# schematic.net
KiCad netlist of a schematic drawn in EAGLE
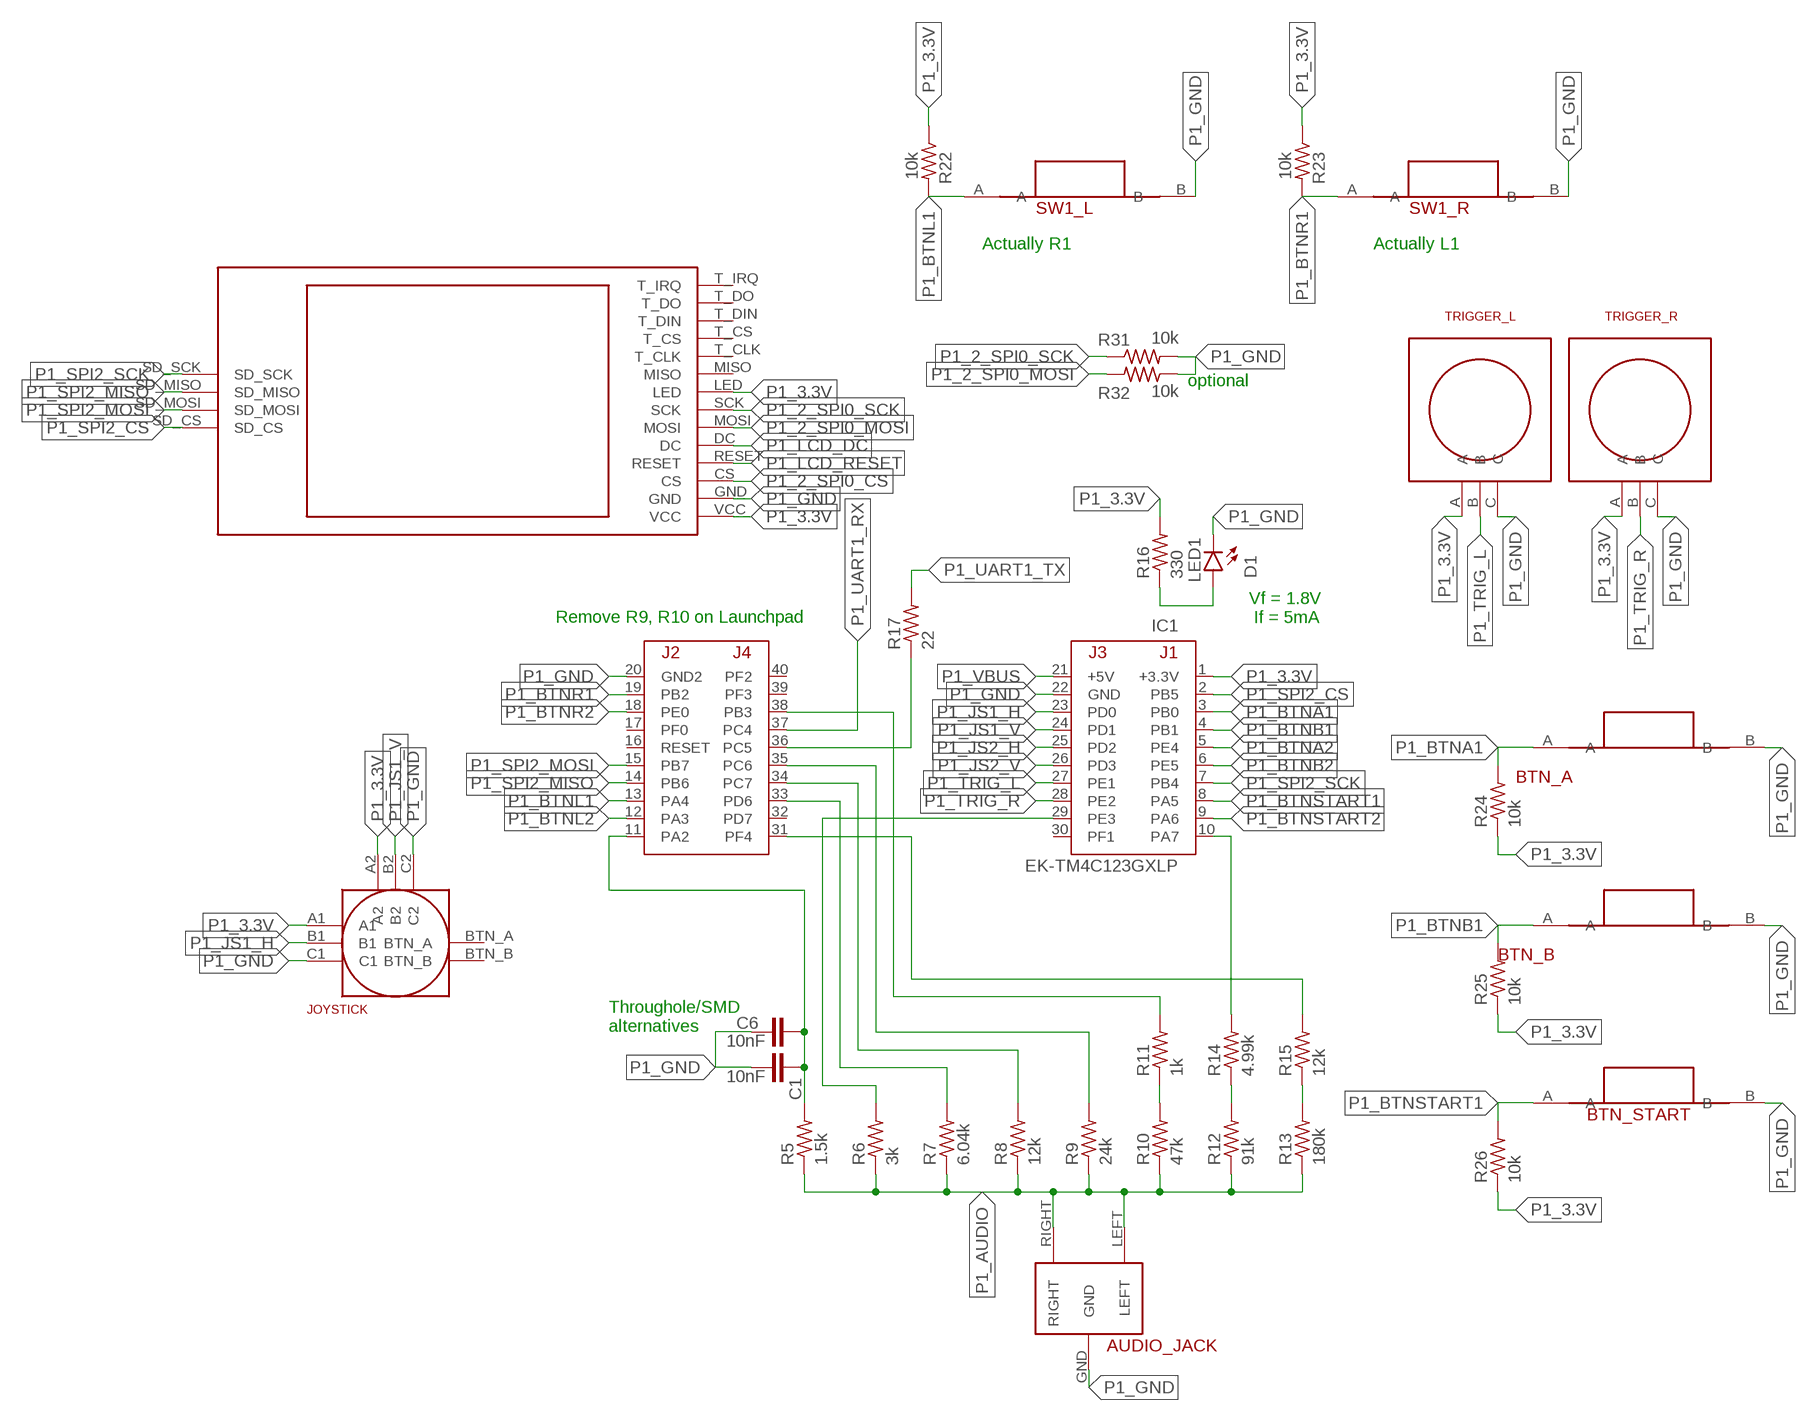
[diagram p0: schematic, sheet 1, part 1 of 2]
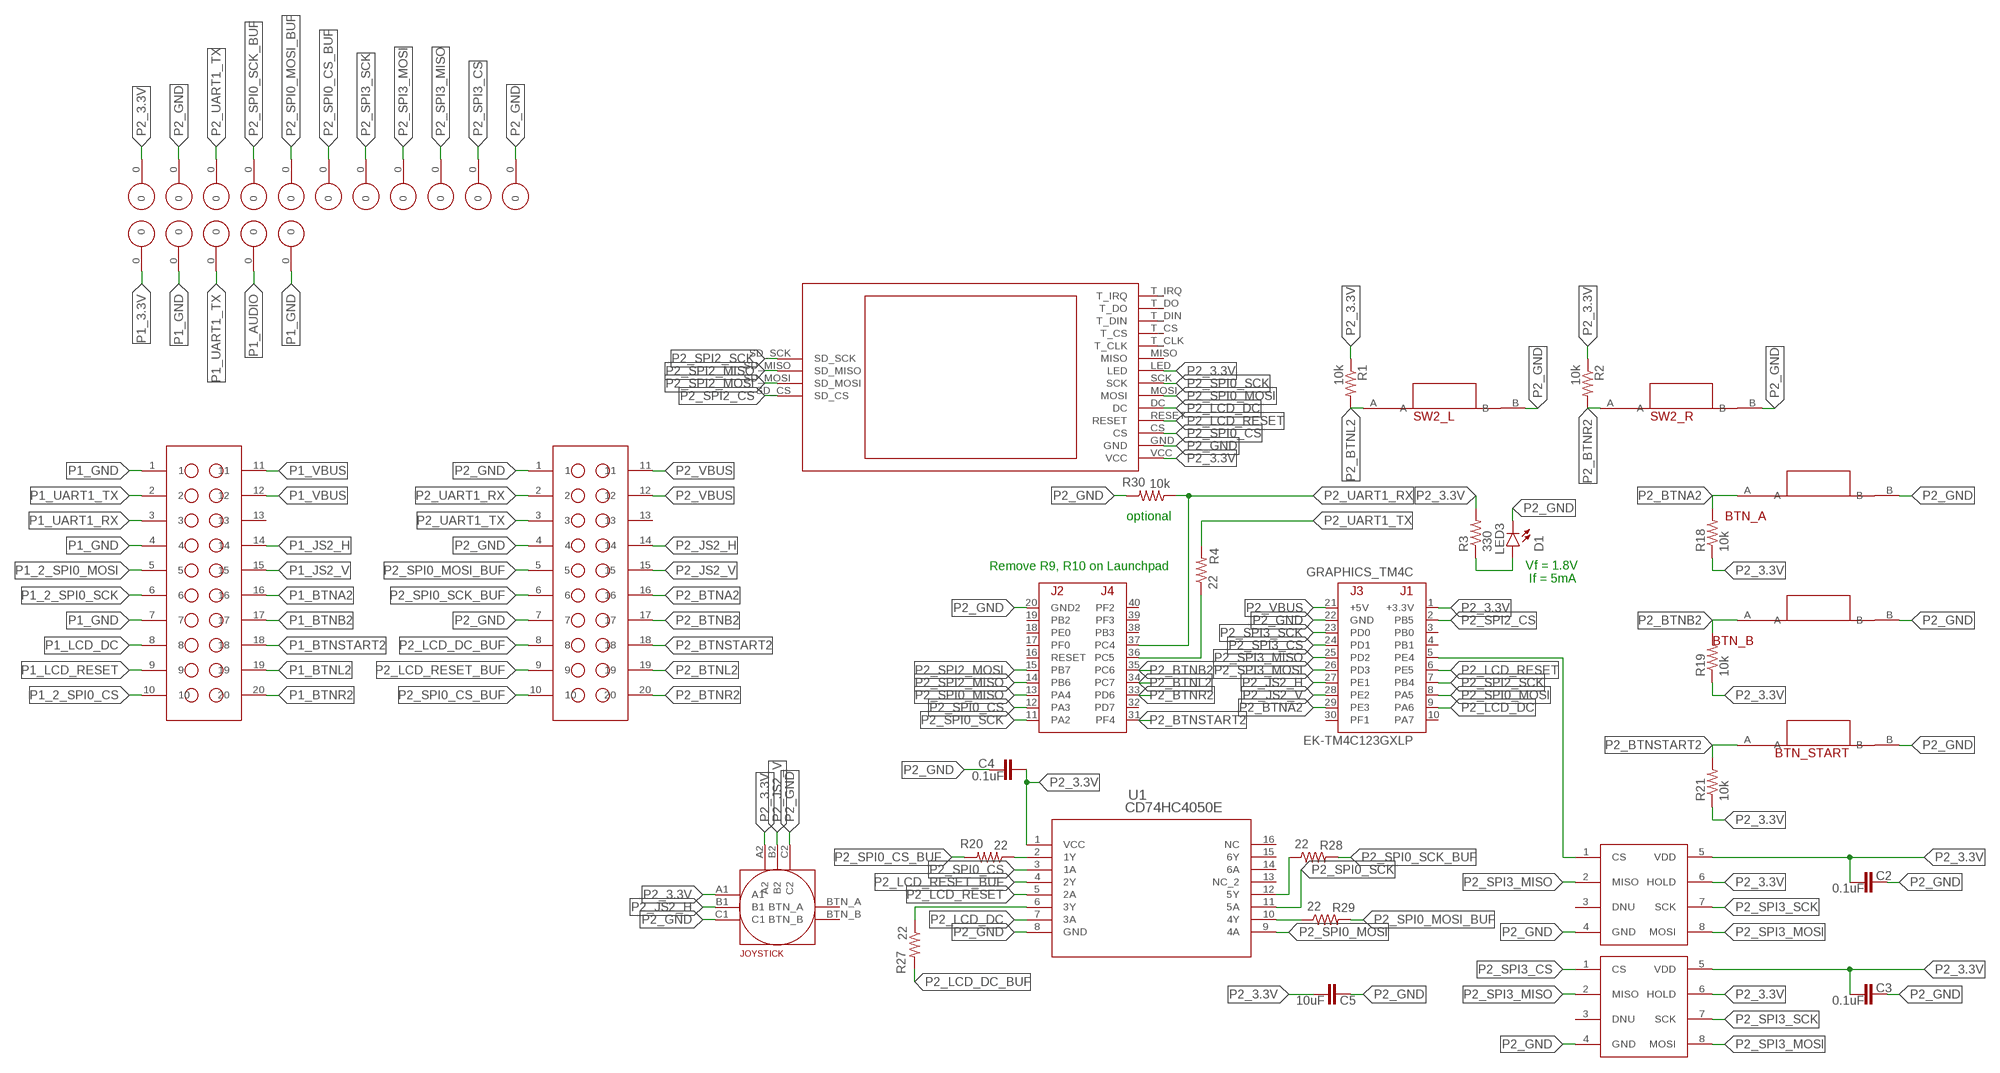
[diagram p1: schematic, sheet 1, part 2 of 2]

(export (version "E")
  (design (tool "Eeschema 10.0.6"))
  (components
    (comp (ref "C1")
      (value "10nF")
      (footprint "eagle-import:C050-024X044")
      (libsource (lib "eagle-import") (part "C-EU050-024X044"))
    )
    (comp (ref "C2")
      (value "0.1uF")
      (footprint "eagle-import:C0805")
      (libsource (lib "eagle-import") (part "C-EUC0805"))
    )
    (comp (ref "C3")
      (value "0.1uF")
      (footprint "eagle-import:C0805")
      (libsource (lib "eagle-import") (part "C-EUC0805"))
    )
    (comp (ref "C4")
      (value "0.1uF")
      (footprint "eagle-import:C0805")
      (libsource (lib "eagle-import") (part "C-EUC0805"))
    )
    (comp (ref "C5")
      (value "10uF")
      (footprint "eagle-import:C0805")
      (libsource (lib "eagle-import") (part "C-EUC0805"))
    )
    (comp (ref "C6")
      (value "10nF")
      (footprint "eagle-import:C0805")
      (libsource (lib "eagle-import") (part "C-EUC0805"))
    )
    (comp (ref "GRAPHICS_TM4C")
      (value "EK-TM4C123GXLP")
      (footprint "eagle-import:TM4C123LAUNCHPAD")
      (fields (field (name "MF") "Texas Instruments") (field (name "MP") "EK-TM4C123GXL"))
      (libsource (lib "eagle-import") (part "EK-TM4C123GXLP"))
    )
    (comp (ref "IC1")
      (value "EK-TM4C123GXLP")
      (footprint "eagle-import:TM4C123LAUNCHPAD")
      (fields (field (name "MF") "Texas Instruments") (field (name "MP") "EK-TM4C123GXL"))
      (libsource (lib "eagle-import") (part "EK-TM4C123GXLP"))
    )
    (comp (ref "LED1")
      (value "D1")
      (footprint "eagle-import:CHIPLED_1206")
      (libsource (lib "eagle-import") (part "LEDCHIPLED_1206"))
    )
    (comp (ref "LED3")
      (value "D1")
      (footprint "eagle-import:CHIPLED_1206")
      (libsource (lib "eagle-import") (part "LEDCHIPLED_1206"))
    )
    (comp (ref "P1_3.3V")
      (value "3.3v")
      (footprint "eagle-import:TESTPOINT")
      (libsource (lib "eagle-import") (part "TESTPOINT"))
    )
    (comp (ref "P1_AUDIO")
      (value "TESTPOINT")
      (footprint "eagle-import:TESTPOINT")
      (libsource (lib "eagle-import") (part "TESTPOINT"))
    )
    (comp (ref "P1_GND")
      (value "TESTPOINT")
      (footprint "eagle-import:TESTPOINT")
      (libsource (lib "eagle-import") (part "TESTPOINT"))
    )
    (comp (ref "P1_GND1")
      (value "TESTPOINT")
      (footprint "eagle-import:TESTPOINT")
      (libsource (lib "eagle-import") (part "TESTPOINT"))
    )
    (comp (ref "P1_LCD")
      (value "ILI9341")
      (footprint "eagle-import:ILI9341")
      (libsource (lib "eagle-import") (part "ILI9341"))
    )
    (comp (ref "P1_UART")
      (value "TESTPOINT")
      (footprint "eagle-import:TESTPOINT")
      (libsource (lib "eagle-import") (part "TESTPOINT"))
    )
    (comp (ref "P2_3.3V")
      (value "TESTPOINT")
      (footprint "eagle-import:TESTPOINT")
      (libsource (lib "eagle-import") (part "TESTPOINT"))
    )
    (comp (ref "P2_GND")
      (value "TESTPOINT")
      (footprint "eagle-import:TESTPOINT")
      (libsource (lib "eagle-import") (part "TESTPOINT"))
    )
    (comp (ref "P2_GND1")
      (value "TESTPOINT")
      (footprint "eagle-import:TESTPOINT")
      (libsource (lib "eagle-import") (part "TESTPOINT"))
    )
    (comp (ref "P2_LCD")
      (value "ILI9341")
      (footprint "eagle-import:ILI9341")
      (libsource (lib "eagle-import") (part "ILI9341"))
    )
    (comp (ref "P2_SPI0_CS_BUF")
      (value "TESTPOINT")
      (footprint "eagle-import:TESTPOINT")
      (libsource (lib "eagle-import") (part "TESTPOINT"))
    )
    (comp (ref "P2_SPI0_MOSI_BUF")
      (value "TESTPOINT")
      (footprint "eagle-import:TESTPOINT")
      (libsource (lib "eagle-import") (part "TESTPOINT"))
    )
    (comp (ref "P2_SPI0_SCK_BUF")
      (value "TESTPOINT")
      (footprint "eagle-import:TESTPOINT")
      (libsource (lib "eagle-import") (part "TESTPOINT"))
    )
    (comp (ref "P2_SPI3_CS")
      (value "TESTPOINT")
      (footprint "eagle-import:TESTPOINT")
      (libsource (lib "eagle-import") (part "TESTPOINT"))
    )
    (comp (ref "P2_SPI3_MISO")
      (value "TESTPOINT")
      (footprint "eagle-import:TESTPOINT")
      (libsource (lib "eagle-import") (part "TESTPOINT"))
    )
    (comp (ref "P2_SPI3_MOSI")
      (value "TESTPOINT")
      (footprint "eagle-import:TESTPOINT")
      (libsource (lib "eagle-import") (part "TESTPOINT"))
    )
    (comp (ref "P2_SPI3_SCK_BUF")
      (value "TESTPOINT")
      (footprint "eagle-import:TESTPOINT")
      (libsource (lib "eagle-import") (part "TESTPOINT"))
    )
    (comp (ref "P2_UART1_TX")
      (value "TESTPOINT")
      (footprint "eagle-import:TESTPOINT")
      (libsource (lib "eagle-import") (part "TESTPOINT"))
    )
    (comp (ref "R1")
      (value "10k")
      (footprint "eagle-import:R0805")
      (libsource (lib "eagle-import") (part "R-US_R0805"))
    )
    (comp (ref "R2")
      (value "10k")
      (footprint "eagle-import:R0805")
      (libsource (lib "eagle-import") (part "R-US_R0805"))
    )
    (comp (ref "R3")
      (value "330")
      (footprint "eagle-import:R0805")
      (libsource (lib "eagle-import") (part "R-US_R0805"))
    )
    (comp (ref "R4")
      (value "22")
      (footprint "eagle-import:R0805")
      (libsource (lib "eagle-import") (part "R-US_R0805"))
    )
    (comp (ref "R5")
      (value "1.5k")
      (footprint "eagle-import:R0805")
      (libsource (lib "eagle-import") (part "R-US_R0805"))
    )
    (comp (ref "R6")
      (value "3k")
      (footprint "eagle-import:R0805")
      (libsource (lib "eagle-import") (part "R-US_R0805"))
    )
    (comp (ref "R7")
      (value "6.04k")
      (footprint "eagle-import:R0805")
      (libsource (lib "eagle-import") (part "R-US_R0805"))
    )
    (comp (ref "R8")
      (value "12k")
      (footprint "eagle-import:R0805")
      (libsource (lib "eagle-import") (part "R-US_R0805"))
    )
    (comp (ref "R9")
      (value "24k")
      (footprint "eagle-import:R0805")
      (libsource (lib "eagle-import") (part "R-US_R0805"))
    )
    (comp (ref "R10")
      (value "47k")
      (footprint "eagle-import:R0805")
      (libsource (lib "eagle-import") (part "R-US_R0805"))
    )
    (comp (ref "R11")
      (value "1k")
      (footprint "eagle-import:R0805")
      (libsource (lib "eagle-import") (part "R-US_R0805"))
    )
    (comp (ref "R12")
      (value "91k")
      (footprint "eagle-import:R0805")
      (libsource (lib "eagle-import") (part "R-US_R0805"))
    )
    (comp (ref "R13")
      (value "180k")
      (footprint "eagle-import:R0805")
      (libsource (lib "eagle-import") (part "R-US_R0805"))
    )
    (comp (ref "R14")
      (value "4.99k")
      (footprint "eagle-import:R0805")
      (libsource (lib "eagle-import") (part "R-US_R0805"))
    )
    (comp (ref "R15")
      (value "12k")
      (footprint "eagle-import:R0805")
      (libsource (lib "eagle-import") (part "R-US_R0805"))
    )
    (comp (ref "R16")
      (value "330")
      (footprint "eagle-import:R0805")
      (libsource (lib "eagle-import") (part "R-US_R0805"))
    )
    (comp (ref "R17")
      (value "22")
      (footprint "eagle-import:R0805")
      (libsource (lib "eagle-import") (part "R-US_R0805"))
    )
    (comp (ref "R18")
      (value "10k")
      (footprint "eagle-import:R0805")
      (libsource (lib "eagle-import") (part "R-US_R0805"))
    )
    (comp (ref "R19")
      (value "10k")
      (footprint "eagle-import:R0805")
      (libsource (lib "eagle-import") (part "R-US_R0805"))
    )
    (comp (ref "R20")
      (value "22")
      (footprint "eagle-import:R0805")
      (libsource (lib "eagle-import") (part "R-US_R0805"))
    )
    (comp (ref "R21")
      (value "10k")
      (footprint "eagle-import:R0805")
      (libsource (lib "eagle-import") (part "R-US_R0805"))
    )
    (comp (ref "R22")
      (value "10k")
      (footprint "eagle-import:R0805")
      (libsource (lib "eagle-import") (part "R-US_R0805"))
    )
    (comp (ref "R23")
      (value "10k")
      (footprint "eagle-import:R0805")
      (libsource (lib "eagle-import") (part "R-US_R0805"))
    )
    (comp (ref "R24")
      (value "10k")
      (footprint "eagle-import:R0805")
      (libsource (lib "eagle-import") (part "R-US_R0805"))
    )
    (comp (ref "R25")
      (value "10k")
      (footprint "eagle-import:R0805")
      (libsource (lib "eagle-import") (part "R-US_R0805"))
    )
    (comp (ref "R26")
      (value "10k")
      (footprint "eagle-import:R0805")
      (libsource (lib "eagle-import") (part "R-US_R0805"))
    )
    (comp (ref "R27")
      (value "22")
      (footprint "eagle-import:R0805")
      (libsource (lib "eagle-import") (part "R-US_R0805"))
    )
    (comp (ref "R28")
      (value "22")
      (footprint "eagle-import:R0805")
      (libsource (lib "eagle-import") (part "R-US_R0805"))
    )
    (comp (ref "R29")
      (value "22")
      (footprint "eagle-import:R0805")
      (libsource (lib "eagle-import") (part "R-US_R0805"))
    )
    (comp (ref "R30")
      (value "10k")
      (footprint "eagle-import:R0805")
      (libsource (lib "eagle-import") (part "R-US_R0805"))
    )
    (comp (ref "R31")
      (value "10k")
      (footprint "eagle-import:R0805")
      (libsource (lib "eagle-import") (part "R-US_R0805"))
    )
    (comp (ref "R32")
      (value "10k")
      (footprint "eagle-import:R0805")
      (libsource (lib "eagle-import") (part "R-US_R0805"))
    )
    (comp (ref "U$2")
      (value "JOYSTICK")
      (footprint "eagle-import:JOYSTICK")
      (libsource (lib "eagle-import") (part "JOYSTICK"))
    )
    (comp (ref "U$3")
      (value "SW2_R")
      (footprint "eagle-import:SW-1825968-2")
      (libsource (lib "eagle-import") (part "SW-1825968-2"))
    )
    (comp (ref "U$4")
      (value "SW2_L")
      (footprint "eagle-import:SW-1825968-2")
      (libsource (lib "eagle-import") (part "SW-1825968-2"))
    )
    (comp (ref "U$5")
      (value "TRIGGER_L")
      (footprint "eagle-import:TRIGGER_L")
      (libsource (lib "eagle-import") (part "TRIGGER_L"))
    )
    (comp (ref "U$6")
      (value "TRIGGER_R")
      (footprint "eagle-import:TRIGGER_R")
      (libsource (lib "eagle-import") (part "TRIGGER_R"))
    )
    (comp (ref "U$7")
      (value "IS62WVS5128FALL-16NLI")
      (footprint "eagle-import:SOIC127P600X144-8")
      (libsource (lib "eagle-import") (part "IS62WVS5128FALL-16NLI"))
    )
    (comp (ref "U$8")
      (value "IS62WVS5128FALL-16NLI")
      (footprint "eagle-import:SOIC127P600X144-8")
      (libsource (lib "eagle-import") (part "IS62WVS5128FALL-16NLI"))
    )
    (comp (ref "U$10")
      (value "AUDIO_JACK")
      (footprint "eagle-import:AUDIO_JACK")
      (libsource (lib "eagle-import") (part "AUDIO_JACK"))
    )
    (comp (ref "U$11")
      (value "10X2_HEADER")
      (footprint "eagle-import:10X2_HEADER")
      (libsource (lib "eagle-import") (part "10X2_HEADER"))
    )
    (comp (ref "U$12")
      (value "10X2_HEADER")
      (footprint "eagle-import:10X2_HEADER")
      (libsource (lib "eagle-import") (part "10X2_HEADER"))
    )
    (comp (ref "U$13")
      (value "JOYSTICK")
      (footprint "eagle-import:JOYSTICK")
      (libsource (lib "eagle-import") (part "JOYSTICK"))
    )
    (comp (ref "U$14")
      (value "BTN_A")
      (footprint "eagle-import:BUTTON")
      (libsource (lib "eagle-import") (part "BUTTON"))
    )
    (comp (ref "U$15")
      (value "BTN_B")
      (footprint "eagle-import:BUTTON")
      (libsource (lib "eagle-import") (part "BUTTON"))
    )
    (comp (ref "U$17")
      (value "BTN_START")
      (footprint "eagle-import:BUTTON")
      (libsource (lib "eagle-import") (part "BUTTON"))
    )
    (comp (ref "U$18")
      (value "SW1_R")
      (footprint "eagle-import:SW-1825968-2")
      (libsource (lib "eagle-import") (part "SW-1825968-2"))
    )
    (comp (ref "U$19")
      (value "SW1_L")
      (footprint "eagle-import:SW-1825968-2")
      (libsource (lib "eagle-import") (part "SW-1825968-2"))
    )
    (comp (ref "U$20")
      (value "BTN_A")
      (footprint "eagle-import:BUTTON")
      (libsource (lib "eagle-import") (part "BUTTON"))
    )
    (comp (ref "U$23")
      (value "BTN_B")
      (footprint "eagle-import:BUTTON")
      (libsource (lib "eagle-import") (part "BUTTON"))
    )
    (comp (ref "U$24")
      (value "BTN_START")
      (footprint "eagle-import:BUTTON")
      (libsource (lib "eagle-import") (part "BUTTON"))
    )
    (comp (ref "U1")
      (value "CD74HC4050E")
      (footprint "eagle-import:N16")
      (libsource (lib "eagle-import") (part "CD74HC4050E"))
    )
  )
  (nets
    (net (code "1") (name "Net-(GRAPHICS_TM4C-PC5)") (class "Default")
      (node (ref "GRAPHICS_TM4C") (pin "36") (pinfunction "PC5_36") (pintype "bidirectional"))
      (node (ref "R4") (pin "1") (pinfunction "1_1") (pintype "passive"))
    )
    (net (code "2") (name "Net-(GRAPHICS_TM4C-PE4)") (class "Default")
      (node (ref "GRAPHICS_TM4C") (pin "5") (pinfunction "PE4_5") (pintype "bidirectional"))
      (node (ref "U$8") (pin "1") (pinfunction "CS_1") (pintype "bidirectional"))
    )
    (net (code "3") (name "Net-(IC1-PA2)") (class "Default")
      (node (ref "C1") (pin "1") (pinfunction "1_1") (pintype "passive"))
      (node (ref "C6") (pin "1") (pinfunction "1_1") (pintype "passive"))
      (node (ref "IC1") (pin "11") (pinfunction "PA2_11") (pintype "bidirectional"))
      (node (ref "R5") (pin "2") (pinfunction "2_2") (pintype "passive"))
    )
    (net (code "4") (name "Net-(IC1-PA7)") (class "Default")
      (node (ref "IC1") (pin "10") (pinfunction "PA7_10") (pintype "bidirectional"))
      (node (ref "R14") (pin "2") (pinfunction "2_2") (pintype "passive"))
    )
    (net (code "5") (name "Net-(IC1-PB3)") (class "Default")
      (node (ref "IC1") (pin "38") (pinfunction "PB3_38") (pintype "bidirectional"))
      (node (ref "R11") (pin "2") (pinfunction "2_2") (pintype "passive"))
    )
    (net (code "6") (name "Net-(IC1-PC5)") (class "Default")
      (node (ref "IC1") (pin "36") (pinfunction "PC5_36") (pintype "bidirectional"))
      (node (ref "R17") (pin "1") (pinfunction "1_1") (pintype "passive"))
    )
    (net (code "7") (name "Net-(IC1-PC6)") (class "Default")
      (node (ref "IC1") (pin "35") (pinfunction "PC6_35") (pintype "bidirectional"))
      (node (ref "R9") (pin "2") (pinfunction "2_2") (pintype "passive"))
    )
    (net (code "8") (name "Net-(IC1-PC7)") (class "Default")
      (node (ref "IC1") (pin "34") (pinfunction "PC7_34") (pintype "bidirectional"))
      (node (ref "R8") (pin "2") (pinfunction "2_2") (pintype "passive"))
    )
    (net (code "9") (name "Net-(IC1-PD6)") (class "Default")
      (node (ref "IC1") (pin "33") (pinfunction "PD6_33") (pintype "bidirectional"))
      (node (ref "R7") (pin "2") (pinfunction "2_2") (pintype "passive"))
    )
    (net (code "10") (name "Net-(IC1-PE3)") (class "Default")
      (node (ref "IC1") (pin "29") (pinfunction "PE3_29") (pintype "bidirectional"))
      (node (ref "R6") (pin "2") (pinfunction "2_2") (pintype "passive"))
    )
    (net (code "11") (name "Net-(IC1-PF4)") (class "Default")
      (node (ref "IC1") (pin "31") (pinfunction "PF4_31") (pintype "bidirectional"))
      (node (ref "R15") (pin "2") (pinfunction "2_2") (pintype "passive"))
    )
    (net (code "12") (name "Net-(LED1-PadA)") (class "Default")
      (node (ref "LED1") (pin "A") (pinfunction "A_A") (pintype "passive"))
      (node (ref "R16") (pin "1") (pinfunction "1_1") (pintype "passive"))
    )
    (net (code "13") (name "Net-(LED3-PadA)") (class "Default")
      (node (ref "LED3") (pin "A") (pinfunction "A_A") (pintype "passive"))
      (node (ref "R3") (pin "1") (pinfunction "1_1") (pintype "passive"))
    )
    (net (code "14") (name "Net-(R10-Pad2)") (class "Default")
      (node (ref "R10") (pin "2") (pinfunction "2_2") (pintype "passive"))
      (node (ref "R11") (pin "1") (pinfunction "1_1") (pintype "passive"))
    )
    (net (code "15") (name "Net-(R12-Pad2)") (class "Default")
      (node (ref "R12") (pin "2") (pinfunction "2_2") (pintype "passive"))
      (node (ref "R14") (pin "1") (pinfunction "1_1") (pintype "passive"))
    )
    (net (code "16") (name "Net-(R13-Pad2)") (class "Default")
      (node (ref "R13") (pin "2") (pinfunction "2_2") (pintype "passive"))
      (node (ref "R15") (pin "1") (pinfunction "1_1") (pintype "passive"))
    )
    (net (code "17") (name "Net-(U1-1Y)") (class "Default")
      (node (ref "R20") (pin "1") (pinfunction "1_1") (pintype "passive"))
      (node (ref "U1") (pin "2") (pinfunction "1Y_2") (pintype "output"))
    )
    (net (code "18") (name "Net-(U1-3Y)") (class "Default")
      (node (ref "R27") (pin "1") (pinfunction "1_1") (pintype "passive"))
      (node (ref "U1") (pin "6") (pinfunction "3Y_6") (pintype "output"))
    )
    (net (code "19") (name "Net-(U1-4Y)") (class "Default")
      (node (ref "R29") (pin "1") (pinfunction "1_1") (pintype "passive"))
      (node (ref "U1") (pin "10") (pinfunction "4Y_10") (pintype "output"))
    )
    (net (code "20") (name "Net-(U1-5Y)") (class "Default")
      (node (ref "R28") (pin "1") (pinfunction "1_1") (pintype "passive"))
      (node (ref "U1") (pin "12") (pinfunction "5Y_12") (pintype "output"))
    )
    (net (code "21") (name "P1_2_SPI0_CS") (class "Default")
      (node (ref "P1_LCD") (pin "CS") (pinfunction "CS_CS") (pintype "bidirectional"))
      (node (ref "U$11") (pin "10") (pinfunction "10_10") (pintype "bidirectional"))
    )
    (net (code "22") (name "P1_2_SPI0_MOSI") (class "Default")
      (node (ref "P1_LCD") (pin "MOSI") (pinfunction "MOSI_MOSI") (pintype "bidirectional"))
      (node (ref "R32") (pin "2") (pinfunction "2_2") (pintype "passive"))
      (node (ref "U$11") (pin "5") (pinfunction "5_5") (pintype "bidirectional"))
    )
    (net (code "23") (name "P1_2_SPI0_SCK") (class "Default")
      (node (ref "P1_LCD") (pin "SCK") (pinfunction "SCK_SCK") (pintype "bidirectional"))
      (node (ref "R31") (pin "1") (pinfunction "1_1") (pintype "passive"))
      (node (ref "U$11") (pin "6") (pinfunction "6_6") (pintype "bidirectional"))
    )
    (net (code "24") (name "P1_3.3V") (class "Default")
      (node (ref "IC1") (pin "1") (pinfunction "+3.3V_1") (pintype "power_in"))
      (node (ref "P1_3.3V") (pin "0") (pinfunction "0_0") (pintype "bidirectional"))
      (node (ref "P1_LCD") (pin "LED") (pinfunction "LED_LED") (pintype "bidirectional"))
      (node (ref "P1_LCD") (pin "VCC") (pinfunction "VCC_VCC") (pintype "bidirectional"))
      (node (ref "R16") (pin "2") (pinfunction "2_2") (pintype "passive"))
      (node (ref "R22") (pin "1") (pinfunction "1_1") (pintype "passive"))
      (node (ref "R23") (pin "1") (pinfunction "1_1") (pintype "passive"))
      (node (ref "R24") (pin "1") (pinfunction "1_1") (pintype "passive"))
      (node (ref "R25") (pin "1") (pinfunction "1_1") (pintype "passive"))
      (node (ref "R26") (pin "1") (pinfunction "1_1") (pintype "passive"))
      (node (ref "U$2") (pin "A1") (pinfunction "A1_A1") (pintype "bidirectional"))
      (node (ref "U$2") (pin "A2") (pinfunction "A2_A2") (pintype "bidirectional"))
      (node (ref "U$5") (pin "A") (pinfunction "A_A") (pintype "bidirectional"))
      (node (ref "U$6") (pin "A") (pinfunction "A_A") (pintype "bidirectional"))
    )
    (net (code "25") (name "P1_AUDIO") (class "Default")
      (node (ref "P1_AUDIO") (pin "0") (pinfunction "0_0") (pintype "bidirectional"))
      (node (ref "R10") (pin "1") (pinfunction "1_1") (pintype "passive"))
      (node (ref "R12") (pin "1") (pinfunction "1_1") (pintype "passive"))
      (node (ref "R13") (pin "1") (pinfunction "1_1") (pintype "passive"))
      (node (ref "R5") (pin "1") (pinfunction "1_1") (pintype "passive"))
      (node (ref "R6") (pin "1") (pinfunction "1_1") (pintype "passive"))
      (node (ref "R7") (pin "1") (pinfunction "1_1") (pintype "passive"))
      (node (ref "R8") (pin "1") (pinfunction "1_1") (pintype "passive"))
      (node (ref "R9") (pin "1") (pinfunction "1_1") (pintype "passive"))
      (node (ref "U$10") (pin "LEFT") (pinfunction "LEFT_LEFT") (pintype "bidirectional"))
      (node (ref "U$10") (pin "RIGHT") (pinfunction "RIGHT_RIGHT") (pintype "bidirectional"))
    )
    (net (code "26") (name "P1_BTNA1") (class "Default")
      (node (ref "IC1") (pin "3") (pinfunction "PB0_3") (pintype "bidirectional"))
      (node (ref "R24") (pin "2") (pinfunction "2_2") (pintype "passive"))
      (node (ref "U$20") (pin "A") (pinfunction "A_A") (pintype "bidirectional"))
    )
    (net (code "27") (name "P1_BTNA2") (class "Default")
      (node (ref "IC1") (pin "5") (pinfunction "PE4_5") (pintype "bidirectional"))
      (node (ref "U$11") (pin "16") (pinfunction "16_16") (pintype "bidirectional"))
    )
    (net (code "28") (name "P1_BTNB1") (class "Default")
      (node (ref "IC1") (pin "4") (pinfunction "PB1_4") (pintype "bidirectional"))
      (node (ref "R25") (pin "2") (pinfunction "2_2") (pintype "passive"))
      (node (ref "U$23") (pin "A") (pinfunction "A_A") (pintype "bidirectional"))
    )
    (net (code "29") (name "P1_BTNB2") (class "Default")
      (node (ref "IC1") (pin "6") (pinfunction "PE5_6") (pintype "bidirectional"))
      (node (ref "U$11") (pin "17") (pinfunction "17_17") (pintype "bidirectional"))
    )
    (net (code "30") (name "P1_BTNL1") (class "Default")
      (node (ref "IC1") (pin "13") (pinfunction "PA4_13") (pintype "bidirectional"))
      (node (ref "R22") (pin "2") (pinfunction "2_2") (pintype "passive"))
      (node (ref "U$19") (pin "A") (pinfunction "A_A") (pintype "bidirectional"))
    )
    (net (code "31") (name "P1_BTNL2") (class "Default")
      (node (ref "IC1") (pin "12") (pinfunction "PA3_12") (pintype "bidirectional"))
      (node (ref "U$11") (pin "19") (pinfunction "19_19") (pintype "bidirectional"))
    )
    (net (code "32") (name "P1_BTNR1") (class "Default")
      (node (ref "IC1") (pin "19") (pinfunction "PB2_19") (pintype "bidirectional"))
      (node (ref "R23") (pin "2") (pinfunction "2_2") (pintype "passive"))
      (node (ref "U$18") (pin "A") (pinfunction "A_A") (pintype "bidirectional"))
    )
    (net (code "33") (name "P1_BTNR2") (class "Default")
      (node (ref "IC1") (pin "18") (pinfunction "PE0_18") (pintype "bidirectional"))
      (node (ref "U$11") (pin "20") (pinfunction "20_20") (pintype "bidirectional"))
    )
    (net (code "34") (name "P1_BTNSTART1") (class "Default")
      (node (ref "IC1") (pin "8") (pinfunction "PA5_8") (pintype "bidirectional"))
      (node (ref "R26") (pin "2") (pinfunction "2_2") (pintype "passive"))
      (node (ref "U$24") (pin "A") (pinfunction "A_A") (pintype "bidirectional"))
    )
    (net (code "35") (name "P1_BTNSTART2") (class "Default")
      (node (ref "IC1") (pin "9") (pinfunction "PA6_9") (pintype "bidirectional"))
      (node (ref "U$11") (pin "18") (pinfunction "18_18") (pintype "bidirectional"))
    )
    (net (code "36") (name "P1_GND") (class "Default")
      (node (ref "C1") (pin "2") (pinfunction "2_2") (pintype "passive"))
      (node (ref "C6") (pin "2") (pinfunction "2_2") (pintype "passive"))
      (node (ref "IC1") (pin "20") (pinfunction "GND2_20") (pintype "power_in"))
      (node (ref "IC1") (pin "22") (pinfunction "GND_22") (pintype "power_in"))
      (node (ref "LED1") (pin "C") (pinfunction "C_C") (pintype "passive"))
      (node (ref "P1_GND") (pin "0") (pinfunction "0_0") (pintype "bidirectional"))
      (node (ref "P1_GND1") (pin "0") (pinfunction "0_0") (pintype "bidirectional"))
      (node (ref "P1_LCD") (pin "GND") (pinfunction "GND_GND") (pintype "bidirectional"))
      (node (ref "R31") (pin "2") (pinfunction "2_2") (pintype "passive"))
      (node (ref "R32") (pin "1") (pinfunction "1_1") (pintype "passive"))
      (node (ref "U$10") (pin "GND") (pinfunction "GND_GND") (pintype "bidirectional"))
      (node (ref "U$11") (pin "1") (pinfunction "1_1") (pintype "bidirectional"))
      (node (ref "U$11") (pin "4") (pinfunction "4_4") (pintype "bidirectional"))
      (node (ref "U$11") (pin "7") (pinfunction "7_7") (pintype "bidirectional"))
      (node (ref "U$18") (pin "B") (pinfunction "B_B") (pintype "bidirectional"))
      (node (ref "U$19") (pin "B") (pinfunction "B_B") (pintype "bidirectional"))
      (node (ref "U$2") (pin "C1") (pinfunction "C1_C1") (pintype "bidirectional"))
      (node (ref "U$2") (pin "C2") (pinfunction "C2_C2") (pintype "bidirectional"))
      (node (ref "U$20") (pin "B") (pinfunction "B_B") (pintype "bidirectional"))
      (node (ref "U$23") (pin "B") (pinfunction "B_B") (pintype "bidirectional"))
      (node (ref "U$24") (pin "B") (pinfunction "B_B") (pintype "bidirectional"))
      (node (ref "U$5") (pin "C") (pinfunction "C_C") (pintype "bidirectional"))
      (node (ref "U$6") (pin "C") (pinfunction "C_C") (pintype "bidirectional"))
    )
    (net (code "37") (name "P1_JS1_H") (class "Default")
      (node (ref "IC1") (pin "23") (pinfunction "PD0_23") (pintype "bidirectional"))
      (node (ref "U$2") (pin "B1") (pinfunction "B1_B1") (pintype "bidirectional"))
    )
    (net (code "38") (name "P1_JS1_V") (class "Default")
      (node (ref "IC1") (pin "24") (pinfunction "PD1_24") (pintype "bidirectional"))
      (node (ref "U$2") (pin "B2") (pinfunction "B2_B2") (pintype "bidirectional"))
    )
    (net (code "39") (name "P1_JS2_H") (class "Default")
      (node (ref "IC1") (pin "25") (pinfunction "PD2_25") (pintype "bidirectional"))
      (node (ref "U$11") (pin "14") (pinfunction "14_14") (pintype "bidirectional"))
    )
    (net (code "40") (name "P1_JS2_V") (class "Default")
      (node (ref "IC1") (pin "26") (pinfunction "PD3_26") (pintype "bidirectional"))
      (node (ref "U$11") (pin "15") (pinfunction "15_15") (pintype "bidirectional"))
    )
    (net (code "41") (name "P1_LCD_DC") (class "Default")
      (node (ref "P1_LCD") (pin "DC") (pinfunction "DC_DC") (pintype "bidirectional"))
      (node (ref "U$11") (pin "8") (pinfunction "8_8") (pintype "bidirectional"))
    )
    (net (code "42") (name "P1_LCD_RESET") (class "Default")
      (node (ref "P1_LCD") (pin "RESET") (pinfunction "RESET_RESET") (pintype "bidirectional"))
      (node (ref "U$11") (pin "9") (pinfunction "9_9") (pintype "bidirectional"))
    )
    (net (code "43") (name "P1_SPI2_CS") (class "Default")
      (node (ref "IC1") (pin "2") (pinfunction "PB5_2") (pintype "bidirectional"))
      (node (ref "P1_LCD") (pin "SD_CS") (pinfunction "SD_CS_SD_CS") (pintype "bidirectional"))
    )
    (net (code "44") (name "P1_SPI2_MISO") (class "Default")
      (node (ref "IC1") (pin "14") (pinfunction "PB6_14") (pintype "bidirectional"))
      (node (ref "P1_LCD") (pin "SD_MISO") (pinfunction "SD_MISO_SD_MISO") (pintype "bidirectional"))
    )
    (net (code "45") (name "P1_SPI2_MOSI") (class "Default")
      (node (ref "IC1") (pin "15") (pinfunction "PB7_15") (pintype "bidirectional"))
      (node (ref "P1_LCD") (pin "SD_MOSI") (pinfunction "SD_MOSI_SD_MOSI") (pintype "bidirectional"))
    )
    (net (code "46") (name "P1_SPI2_SCK") (class "Default")
      (node (ref "IC1") (pin "7") (pinfunction "PB4_7") (pintype "bidirectional"))
      (node (ref "P1_LCD") (pin "SD_SCK") (pinfunction "SD_SCK_SD_SCK") (pintype "bidirectional"))
    )
    (net (code "47") (name "P1_TRIG_L") (class "Default")
      (node (ref "IC1") (pin "27") (pinfunction "PE1_27") (pintype "bidirectional"))
      (node (ref "U$5") (pin "B") (pinfunction "B_B") (pintype "bidirectional"))
    )
    (net (code "48") (name "P1_TRIG_R") (class "Default")
      (node (ref "IC1") (pin "28") (pinfunction "PE2_28") (pintype "bidirectional"))
      (node (ref "U$6") (pin "B") (pinfunction "B_B") (pintype "bidirectional"))
    )
    (net (code "49") (name "P1_UART1_RX") (class "Default")
      (node (ref "IC1") (pin "37") (pinfunction "PC4_37") (pintype "bidirectional"))
      (node (ref "U$11") (pin "3") (pinfunction "3_3") (pintype "bidirectional"))
    )
    (net (code "50") (name "P1_UART1_TX") (class "Default")
      (node (ref "P1_UART") (pin "0") (pinfunction "0_0") (pintype "bidirectional"))
      (node (ref "R17") (pin "2") (pinfunction "2_2") (pintype "passive"))
      (node (ref "U$11") (pin "2") (pinfunction "2_2") (pintype "bidirectional"))
    )
    (net (code "51") (name "P1_VBUS") (class "Default")
      (node (ref "IC1") (pin "21") (pinfunction "+5V_21") (pintype "power_in"))
      (node (ref "U$11") (pin "11") (pinfunction "11_11") (pintype "bidirectional"))
      (node (ref "U$11") (pin "12") (pinfunction "12_12") (pintype "bidirectional"))
    )
    (net (code "52") (name "P2_3.3V") (class "Default")
      (node (ref "C2") (pin "2") (pinfunction "2_2") (pintype "passive"))
      (node (ref "C3") (pin "2") (pinfunction "2_2") (pintype "passive"))
      (node (ref "C4") (pin "1") (pinfunction "1_1") (pintype "passive"))
      (node (ref "C5") (pin "2") (pinfunction "2_2") (pintype "passive"))
      (node (ref "GRAPHICS_TM4C") (pin "1") (pinfunction "+3.3V_1") (pintype "power_in"))
      (node (ref "P2_3.3V") (pin "0") (pinfunction "0_0") (pintype "bidirectional"))
      (node (ref "P2_LCD") (pin "LED") (pinfunction "LED_LED") (pintype "bidirectional"))
      (node (ref "P2_LCD") (pin "VCC") (pinfunction "VCC_VCC") (pintype "bidirectional"))
      (node (ref "R1") (pin "1") (pinfunction "1_1") (pintype "passive"))
      (node (ref "R18") (pin "1") (pinfunction "1_1") (pintype "passive"))
      (node (ref "R19") (pin "1") (pinfunction "1_1") (pintype "passive"))
      (node (ref "R2") (pin "1") (pinfunction "1_1") (pintype "passive"))
      (node (ref "R21") (pin "1") (pinfunction "1_1") (pintype "passive"))
      (node (ref "R3") (pin "2") (pinfunction "2_2") (pintype "passive"))
      (node (ref "U$13") (pin "A1") (pinfunction "A1_A1") (pintype "bidirectional"))
      (node (ref "U$13") (pin "A2") (pinfunction "A2_A2") (pintype "bidirectional"))
      (node (ref "U$7") (pin "5") (pinfunction "VDD_5") (pintype "bidirectional"))
      (node (ref "U$7") (pin "6") (pinfunction "HOLD_6") (pintype "bidirectional"))
      (node (ref "U$8") (pin "5") (pinfunction "VDD_5") (pintype "bidirectional"))
      (node (ref "U$8") (pin "6") (pinfunction "HOLD_6") (pintype "bidirectional"))
      (node (ref "U1") (pin "1") (pinfunction "VCC_1") (pintype "passive"))
    )
    (net (code "53") (name "P2_BTNA2") (class "Default")
      (node (ref "GRAPHICS_TM4C") (pin "29") (pinfunction "PE3_29") (pintype "bidirectional"))
      (node (ref "R18") (pin "2") (pinfunction "2_2") (pintype "passive"))
      (node (ref "U$12") (pin "16") (pinfunction "16_16") (pintype "bidirectional"))
      (node (ref "U$14") (pin "A") (pinfunction "A_A") (pintype "bidirectional"))
    )
    (net (code "54") (name "P2_BTNB2") (class "Default")
      (node (ref "GRAPHICS_TM4C") (pin "35") (pinfunction "PC6_35") (pintype "bidirectional"))
      (node (ref "R19") (pin "2") (pinfunction "2_2") (pintype "passive"))
      (node (ref "U$12") (pin "17") (pinfunction "17_17") (pintype "bidirectional"))
      (node (ref "U$15") (pin "A") (pinfunction "A_A") (pintype "bidirectional"))
    )
    (net (code "55") (name "P2_BTNL2") (class "Default")
      (node (ref "GRAPHICS_TM4C") (pin "34") (pinfunction "PC7_34") (pintype "bidirectional"))
      (node (ref "R1") (pin "2") (pinfunction "2_2") (pintype "passive"))
      (node (ref "U$12") (pin "19") (pinfunction "19_19") (pintype "bidirectional"))
      (node (ref "U$4") (pin "A") (pinfunction "A_A") (pintype "bidirectional"))
    )
    (net (code "56") (name "P2_BTNR2") (class "Default")
      (node (ref "GRAPHICS_TM4C") (pin "33") (pinfunction "PD6_33") (pintype "bidirectional"))
      (node (ref "R2") (pin "2") (pinfunction "2_2") (pintype "passive"))
      (node (ref "U$12") (pin "20") (pinfunction "20_20") (pintype "bidirectional"))
      (node (ref "U$3") (pin "A") (pinfunction "A_A") (pintype "bidirectional"))
    )
    (net (code "57") (name "P2_BTNSTART2") (class "Default")
      (node (ref "GRAPHICS_TM4C") (pin "31") (pinfunction "PF4_31") (pintype "bidirectional"))
      (node (ref "R21") (pin "2") (pinfunction "2_2") (pintype "passive"))
      (node (ref "U$12") (pin "18") (pinfunction "18_18") (pintype "bidirectional"))
      (node (ref "U$17") (pin "A") (pinfunction "A_A") (pintype "bidirectional"))
    )
    (net (code "58") (name "P2_GND") (class "Default")
      (node (ref "C2") (pin "1") (pinfunction "1_1") (pintype "passive"))
      (node (ref "C3") (pin "1") (pinfunction "1_1") (pintype "passive"))
      (node (ref "C4") (pin "2") (pinfunction "2_2") (pintype "passive"))
      (node (ref "C5") (pin "1") (pinfunction "1_1") (pintype "passive"))
      (node (ref "GRAPHICS_TM4C") (pin "20") (pinfunction "GND2_20") (pintype "power_in"))
      (node (ref "GRAPHICS_TM4C") (pin "22") (pinfunction "GND_22") (pintype "power_in"))
      (node (ref "LED3") (pin "C") (pinfunction "C_C") (pintype "passive"))
      (node (ref "P2_GND") (pin "0") (pinfunction "0_0") (pintype "bidirectional"))
      (node (ref "P2_GND1") (pin "0") (pinfunction "0_0") (pintype "bidirectional"))
      (node (ref "P2_LCD") (pin "GND") (pinfunction "GND_GND") (pintype "bidirectional"))
      (node (ref "R30") (pin "2") (pinfunction "2_2") (pintype "passive"))
      (node (ref "U$12") (pin "1") (pinfunction "1_1") (pintype "bidirectional"))
      (node (ref "U$12") (pin "4") (pinfunction "4_4") (pintype "bidirectional"))
      (node (ref "U$12") (pin "7") (pinfunction "7_7") (pintype "bidirectional"))
      (node (ref "U$13") (pin "C1") (pinfunction "C1_C1") (pintype "bidirectional"))
      (node (ref "U$13") (pin "C2") (pinfunction "C2_C2") (pintype "bidirectional"))
      (node (ref "U$14") (pin "B") (pinfunction "B_B") (pintype "bidirectional"))
      (node (ref "U$15") (pin "B") (pinfunction "B_B") (pintype "bidirectional"))
      (node (ref "U$17") (pin "B") (pinfunction "B_B") (pintype "bidirectional"))
      (node (ref "U$3") (pin "B") (pinfunction "B_B") (pintype "bidirectional"))
      (node (ref "U$4") (pin "B") (pinfunction "B_B") (pintype "bidirectional"))
      (node (ref "U$7") (pin "4") (pinfunction "GND_4") (pintype "bidirectional"))
      (node (ref "U$8") (pin "4") (pinfunction "GND_4") (pintype "bidirectional"))
      (node (ref "U1") (pin "8") (pinfunction "GND_8") (pintype "passive"))
    )
    (net (code "59") (name "P2_JS2_H") (class "Default")
      (node (ref "GRAPHICS_TM4C") (pin "27") (pinfunction "PE1_27") (pintype "bidirectional"))
      (node (ref "U$12") (pin "14") (pinfunction "14_14") (pintype "bidirectional"))
      (node (ref "U$13") (pin "B1") (pinfunction "B1_B1") (pintype "bidirectional"))
    )
    (net (code "60") (name "P2_JS2_V") (class "Default")
      (node (ref "GRAPHICS_TM4C") (pin "28") (pinfunction "PE2_28") (pintype "bidirectional"))
      (node (ref "U$12") (pin "15") (pinfunction "15_15") (pintype "bidirectional"))
      (node (ref "U$13") (pin "B2") (pinfunction "B2_B2") (pintype "bidirectional"))
    )
    (net (code "61") (name "P2_LCD_DC") (class "Default")
      (node (ref "GRAPHICS_TM4C") (pin "9") (pinfunction "PA6_9") (pintype "bidirectional"))
      (node (ref "P2_LCD") (pin "DC") (pinfunction "DC_DC") (pintype "bidirectional"))
      (node (ref "U1") (pin "7") (pinfunction "3A_7") (pintype "input"))
    )
    (net (code "62") (name "P2_LCD_DC_BUF") (class "Default")
      (node (ref "R27") (pin "2") (pinfunction "2_2") (pintype "passive"))
      (node (ref "U$12") (pin "8") (pinfunction "8_8") (pintype "bidirectional"))
    )
    (net (code "63") (name "P2_LCD_RESET") (class "Default")
      (node (ref "GRAPHICS_TM4C") (pin "6") (pinfunction "PE5_6") (pintype "bidirectional"))
      (node (ref "P2_LCD") (pin "RESET") (pinfunction "RESET_RESET") (pintype "bidirectional"))
      (node (ref "U1") (pin "5") (pinfunction "2A_5") (pintype "input"))
    )
    (net (code "64") (name "P2_LCD_RESET_BUF") (class "Default")
      (node (ref "U$12") (pin "9") (pinfunction "9_9") (pintype "bidirectional"))
      (node (ref "U1") (pin "4") (pinfunction "2Y_4") (pintype "output"))
    )
    (net (code "65") (name "P2_SPI0_CS") (class "Default")
      (node (ref "GRAPHICS_TM4C") (pin "12") (pinfunction "PA3_12") (pintype "bidirectional"))
      (node (ref "P2_LCD") (pin "CS") (pinfunction "CS_CS") (pintype "bidirectional"))
      (node (ref "U1") (pin "3") (pinfunction "1A_3") (pintype "input"))
    )
    (net (code "66") (name "P2_SPI0_CS_BUF") (class "Default")
      (node (ref "P2_SPI0_CS_BUF") (pin "0") (pinfunction "0_0") (pintype "bidirectional"))
      (node (ref "R20") (pin "2") (pinfunction "2_2") (pintype "passive"))
      (node (ref "U$12") (pin "10") (pinfunction "10_10") (pintype "bidirectional"))
    )
    (net (code "67") (name "P2_SPI0_MISO") (class "Default")
      (node (ref "GRAPHICS_TM4C") (pin "13") (pinfunction "PA4_13") (pintype "bidirectional"))
    )
    (net (code "68") (name "P2_SPI0_MOSI") (class "Default")
      (node (ref "GRAPHICS_TM4C") (pin "8") (pinfunction "PA5_8") (pintype "bidirectional"))
      (node (ref "P2_LCD") (pin "MOSI") (pinfunction "MOSI_MOSI") (pintype "bidirectional"))
      (node (ref "U1") (pin "9") (pinfunction "4A_9") (pintype "input"))
    )
    (net (code "69") (name "P2_SPI0_MOSI_BUF") (class "Default")
      (node (ref "P2_SPI0_MOSI_BUF") (pin "0") (pinfunction "0_0") (pintype "bidirectional"))
      (node (ref "R29") (pin "2") (pinfunction "2_2") (pintype "passive"))
      (node (ref "U$12") (pin "5") (pinfunction "5_5") (pintype "bidirectional"))
    )
    (net (code "70") (name "P2_SPI0_SCK") (class "Default")
      (node (ref "GRAPHICS_TM4C") (pin "11") (pinfunction "PA2_11") (pintype "bidirectional"))
      (node (ref "P2_LCD") (pin "SCK") (pinfunction "SCK_SCK") (pintype "bidirectional"))
      (node (ref "U1") (pin "11") (pinfunction "5A_11") (pintype "input"))
    )
    (net (code "71") (name "P2_SPI0_SCK_BUF") (class "Default")
      (node (ref "P2_SPI0_SCK_BUF") (pin "0") (pinfunction "0_0") (pintype "bidirectional"))
      (node (ref "R28") (pin "2") (pinfunction "2_2") (pintype "passive"))
      (node (ref "U$12") (pin "6") (pinfunction "6_6") (pintype "bidirectional"))
    )
    (net (code "72") (name "P2_SPI2_CS") (class "Default")
      (node (ref "GRAPHICS_TM4C") (pin "2") (pinfunction "PB5_2") (pintype "bidirectional"))
      (node (ref "P2_LCD") (pin "SD_CS") (pinfunction "SD_CS_SD_CS") (pintype "bidirectional"))
    )
    (net (code "73") (name "P2_SPI2_MISO") (class "Default")
      (node (ref "GRAPHICS_TM4C") (pin "14") (pinfunction "PB6_14") (pintype "bidirectional"))
      (node (ref "P2_LCD") (pin "SD_MISO") (pinfunction "SD_MISO_SD_MISO") (pintype "bidirectional"))
    )
    (net (code "74") (name "P2_SPI2_MOSI") (class "Default")
      (node (ref "GRAPHICS_TM4C") (pin "15") (pinfunction "PB7_15") (pintype "bidirectional"))
      (node (ref "P2_LCD") (pin "SD_MOSI") (pinfunction "SD_MOSI_SD_MOSI") (pintype "bidirectional"))
    )
    (net (code "75") (name "P2_SPI2_SCK") (class "Default")
      (node (ref "GRAPHICS_TM4C") (pin "7") (pinfunction "PB4_7") (pintype "bidirectional"))
      (node (ref "P2_LCD") (pin "SD_SCK") (pinfunction "SD_SCK_SD_SCK") (pintype "bidirectional"))
    )
    (net (code "76") (name "P2_SPI3_CS") (class "Default")
      (node (ref "GRAPHICS_TM4C") (pin "24") (pinfunction "PD1_24") (pintype "bidirectional"))
      (node (ref "P2_SPI3_CS") (pin "0") (pinfunction "0_0") (pintype "bidirectional"))
      (node (ref "U$7") (pin "1") (pinfunction "CS_1") (pintype "bidirectional"))
    )
    (net (code "77") (name "P2_SPI3_MISO") (class "Default")
      (node (ref "GRAPHICS_TM4C") (pin "25") (pinfunction "PD2_25") (pintype "bidirectional"))
      (node (ref "P2_SPI3_MISO") (pin "0") (pinfunction "0_0") (pintype "bidirectional"))
      (node (ref "U$7") (pin "2") (pinfunction "MISO_2") (pintype "bidirectional"))
      (node (ref "U$8") (pin "2") (pinfunction "MISO_2") (pintype "bidirectional"))
    )
    (net (code "78") (name "P2_SPI3_MOSI") (class "Default")
      (node (ref "GRAPHICS_TM4C") (pin "26") (pinfunction "PD3_26") (pintype "bidirectional"))
      (node (ref "P2_SPI3_MOSI") (pin "0") (pinfunction "0_0") (pintype "bidirectional"))
      (node (ref "U$7") (pin "8") (pinfunction "MOSI_8") (pintype "bidirectional"))
      (node (ref "U$8") (pin "8") (pinfunction "MOSI_8") (pintype "bidirectional"))
    )
    (net (code "79") (name "P2_SPI3_SCK") (class "Default")
      (node (ref "GRAPHICS_TM4C") (pin "23") (pinfunction "PD0_23") (pintype "bidirectional"))
      (node (ref "P2_SPI3_SCK_BUF") (pin "0") (pinfunction "0_0") (pintype "bidirectional"))
      (node (ref "U$7") (pin "7") (pinfunction "SCK_7") (pintype "bidirectional"))
      (node (ref "U$8") (pin "7") (pinfunction "SCK_7") (pintype "bidirectional"))
    )
    (net (code "80") (name "P2_UART1_RX") (class "Default")
      (node (ref "GRAPHICS_TM4C") (pin "37") (pinfunction "PC4_37") (pintype "bidirectional"))
      (node (ref "R30") (pin "1") (pinfunction "1_1") (pintype "passive"))
      (node (ref "U$12") (pin "2") (pinfunction "2_2") (pintype "bidirectional"))
    )
    (net (code "81") (name "P2_UART1_TX") (class "Default")
      (node (ref "P2_UART1_TX") (pin "0") (pinfunction "0_0") (pintype "bidirectional"))
      (node (ref "R4") (pin "2") (pinfunction "2_2") (pintype "passive"))
      (node (ref "U$12") (pin "3") (pinfunction "3_3") (pintype "bidirectional"))
    )
    (net (code "82") (name "P2_VBUS") (class "Default")
      (node (ref "GRAPHICS_TM4C") (pin "21") (pinfunction "+5V_21") (pintype "power_in"))
      (node (ref "U$12") (pin "11") (pinfunction "11_11") (pintype "bidirectional"))
      (node (ref "U$12") (pin "12") (pinfunction "12_12") (pintype "bidirectional"))
    )
    (net (code "83") (name "unconnected-(GRAPHICS_TM4C-PA7-Pad10)") (class "Default")
      (node (ref "GRAPHICS_TM4C") (pin "10") (pinfunction "PA7_10") (pintype "bidirectional"))
    )
    (net (code "84") (name "unconnected-(GRAPHICS_TM4C-PB0-Pad3)") (class "Default")
      (node (ref "GRAPHICS_TM4C") (pin "3") (pinfunction "PB0_3") (pintype "bidirectional"))
    )
    (net (code "85") (name "unconnected-(GRAPHICS_TM4C-PB1-Pad4)") (class "Default")
      (node (ref "GRAPHICS_TM4C") (pin "4") (pinfunction "PB1_4") (pintype "bidirectional"))
    )
    (net (code "86") (name "unconnected-(GRAPHICS_TM4C-PB2-Pad19)") (class "Default")
      (node (ref "GRAPHICS_TM4C") (pin "19") (pinfunction "PB2_19") (pintype "bidirectional"))
    )
    (net (code "87") (name "unconnected-(GRAPHICS_TM4C-PB3-Pad38)") (class "Default")
      (node (ref "GRAPHICS_TM4C") (pin "38") (pinfunction "PB3_38") (pintype "bidirectional"))
    )
    (net (code "88") (name "unconnected-(GRAPHICS_TM4C-PD7-Pad32)") (class "Default")
      (node (ref "GRAPHICS_TM4C") (pin "32") (pinfunction "PD7_32") (pintype "bidirectional"))
    )
    (net (code "89") (name "unconnected-(GRAPHICS_TM4C-PE0-Pad18)") (class "Default")
      (node (ref "GRAPHICS_TM4C") (pin "18") (pinfunction "PE0_18") (pintype "bidirectional"))
    )
    (net (code "90") (name "unconnected-(GRAPHICS_TM4C-PF0-Pad17)") (class "Default")
      (node (ref "GRAPHICS_TM4C") (pin "17") (pinfunction "PF0_17") (pintype "bidirectional"))
    )
    (net (code "91") (name "unconnected-(GRAPHICS_TM4C-PF1-Pad30)") (class "Default")
      (node (ref "GRAPHICS_TM4C") (pin "30") (pinfunction "PF1_30") (pintype "bidirectional"))
    )
    (net (code "92") (name "unconnected-(GRAPHICS_TM4C-PF2-Pad40)") (class "Default")
      (node (ref "GRAPHICS_TM4C") (pin "40") (pinfunction "PF2_40") (pintype "bidirectional"))
    )
    (net (code "93") (name "unconnected-(GRAPHICS_TM4C-PF3-Pad39)") (class "Default")
      (node (ref "GRAPHICS_TM4C") (pin "39") (pinfunction "PF3_39") (pintype "bidirectional"))
    )
    (net (code "94") (name "unconnected-(GRAPHICS_TM4C-RESET-Pad16)") (class "Default")
      (node (ref "GRAPHICS_TM4C") (pin "16") (pinfunction "RESET_16") (pintype "input"))
    )
    (net (code "95") (name "unconnected-(IC1-PD7-Pad32)") (class "Default")
      (node (ref "IC1") (pin "32") (pinfunction "PD7_32") (pintype "bidirectional"))
    )
    (net (code "96") (name "unconnected-(IC1-PF0-Pad17)") (class "Default")
      (node (ref "IC1") (pin "17") (pinfunction "PF0_17") (pintype "bidirectional"))
    )
    (net (code "97") (name "unconnected-(IC1-PF1-Pad30)") (class "Default")
      (node (ref "IC1") (pin "30") (pinfunction "PF1_30") (pintype "bidirectional"))
    )
    (net (code "98") (name "unconnected-(IC1-PF2-Pad40)") (class "Default")
      (node (ref "IC1") (pin "40") (pinfunction "PF2_40") (pintype "bidirectional"))
    )
    (net (code "99") (name "unconnected-(IC1-PF3-Pad39)") (class "Default")
      (node (ref "IC1") (pin "39") (pinfunction "PF3_39") (pintype "bidirectional"))
    )
    (net (code "100") (name "unconnected-(IC1-RESET-Pad16)") (class "Default")
      (node (ref "IC1") (pin "16") (pinfunction "RESET_16") (pintype "input"))
    )
    (net (code "101") (name "unconnected-(P1_LCD-PadMISO)") (class "Default")
      (node (ref "P1_LCD") (pin "MISO") (pinfunction "MISO_MISO") (pintype "bidirectional"))
    )
    (net (code "102") (name "unconnected-(P1_LCD-PadT_CLK)") (class "Default")
      (node (ref "P1_LCD") (pin "T_CLK") (pinfunction "T_CLK_T_CLK") (pintype "bidirectional"))
    )
    (net (code "103") (name "unconnected-(P1_LCD-PadT_CS)") (class "Default")
      (node (ref "P1_LCD") (pin "T_CS") (pinfunction "T_CS_T_CS") (pintype "bidirectional"))
    )
    (net (code "104") (name "unconnected-(P1_LCD-PadT_DIN)") (class "Default")
      (node (ref "P1_LCD") (pin "T_DIN") (pinfunction "T_DIN_T_DIN") (pintype "bidirectional"))
    )
    (net (code "105") (name "unconnected-(P1_LCD-PadT_DO)") (class "Default")
      (node (ref "P1_LCD") (pin "T_DO") (pinfunction "T_DO_T_DO") (pintype "bidirectional"))
    )
    (net (code "106") (name "unconnected-(P1_LCD-PadT_IRQ)") (class "Default")
      (node (ref "P1_LCD") (pin "T_IRQ") (pinfunction "T_IRQ_T_IRQ") (pintype "bidirectional"))
    )
    (net (code "107") (name "unconnected-(P2_LCD-PadMISO)") (class "Default")
      (node (ref "P2_LCD") (pin "MISO") (pinfunction "MISO_MISO") (pintype "bidirectional"))
    )
    (net (code "108") (name "unconnected-(P2_LCD-PadT_CLK)") (class "Default")
      (node (ref "P2_LCD") (pin "T_CLK") (pinfunction "T_CLK_T_CLK") (pintype "bidirectional"))
    )
    (net (code "109") (name "unconnected-(P2_LCD-PadT_CS)") (class "Default")
      (node (ref "P2_LCD") (pin "T_CS") (pinfunction "T_CS_T_CS") (pintype "bidirectional"))
    )
    (net (code "110") (name "unconnected-(P2_LCD-PadT_DIN)") (class "Default")
      (node (ref "P2_LCD") (pin "T_DIN") (pinfunction "T_DIN_T_DIN") (pintype "bidirectional"))
    )
    (net (code "111") (name "unconnected-(P2_LCD-PadT_DO)") (class "Default")
      (node (ref "P2_LCD") (pin "T_DO") (pinfunction "T_DO_T_DO") (pintype "bidirectional"))
    )
    (net (code "112") (name "unconnected-(P2_LCD-PadT_IRQ)") (class "Default")
      (node (ref "P2_LCD") (pin "T_IRQ") (pinfunction "T_IRQ_T_IRQ") (pintype "bidirectional"))
    )
    (net (code "113") (name "unconnected-(U$2-PadBTN_A)") (class "Default")
      (node (ref "U$2") (pin "BTN_A") (pinfunction "BTN_A_BTN_A") (pintype "bidirectional"))
    )
    (net (code "114") (name "unconnected-(U$2-PadBTN_B)") (class "Default")
      (node (ref "U$2") (pin "BTN_B") (pinfunction "BTN_B_BTN_B") (pintype "bidirectional"))
    )
    (net (code "115") (name "unconnected-(U$7-DNU-Pad3)") (class "Default")
      (node (ref "U$7") (pin "3") (pinfunction "DNU_3") (pintype "bidirectional"))
    )
    (net (code "116") (name "unconnected-(U$8-DNU-Pad3)") (class "Default")
      (node (ref "U$8") (pin "3") (pinfunction "DNU_3") (pintype "bidirectional"))
    )
    (net (code "117") (name "unconnected-(U$11-Pad13)") (class "Default")
      (node (ref "U$11") (pin "13") (pinfunction "13_13") (pintype "bidirectional"))
    )
    (net (code "118") (name "unconnected-(U$12-Pad13)") (class "Default")
      (node (ref "U$12") (pin "13") (pinfunction "13_13") (pintype "bidirectional"))
    )
    (net (code "119") (name "unconnected-(U$13-PadBTN_A)") (class "Default")
      (node (ref "U$13") (pin "BTN_A") (pinfunction "BTN_A_BTN_A") (pintype "bidirectional"))
    )
    (net (code "120") (name "unconnected-(U$13-PadBTN_B)") (class "Default")
      (node (ref "U$13") (pin "BTN_B") (pinfunction "BTN_B_BTN_B") (pintype "bidirectional"))
    )
    (net (code "121") (name "unconnected-(U1-6A-Pad14)") (class "Default")
      (node (ref "U1") (pin "14") (pinfunction "6A_14") (pintype "input"))
    )
    (net (code "122") (name "unconnected-(U1-6Y-Pad15)") (class "Default")
      (node (ref "U1") (pin "15") (pinfunction "6Y_15") (pintype "output"))
    )
    (net (code "123") (name "unconnected-(U1-NC-Pad16)") (class "Default")
      (node (ref "U1") (pin "16") (pinfunction "NC_16") (pintype "no_connect"))
    )
    (net (code "124") (name "unconnected-(U1-NC_2-Pad13)") (class "Default")
      (node (ref "U1") (pin "13") (pinfunction "NC_2_13") (pintype "no_connect"))
    )
  )
)
